# MCUv1_2.net
KiCad netlist of a schematic drawn in Altium Designer
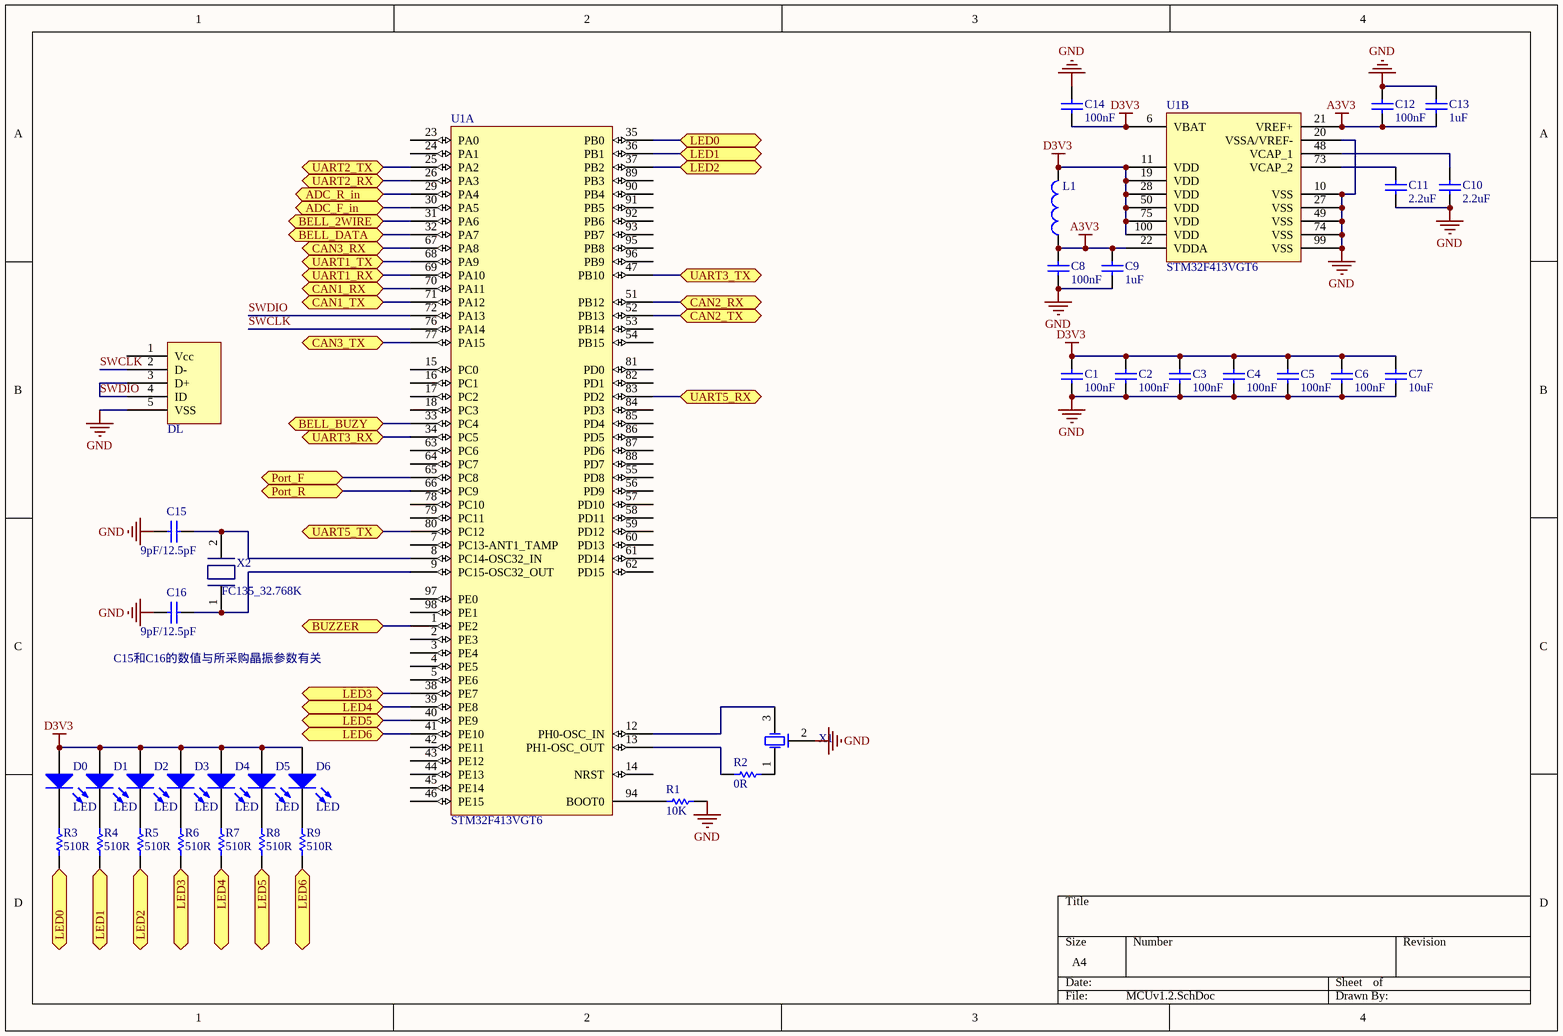
[diagram p0: MCUv1.2.SchDoc]

(export (version "E")
  (design (tool "Eeschema 10.0.6"))
  (components
    (comp (ref "C1")
      (value "100nF")
      (footprint "BinFeng:0402")
      (description "Capacitor")
      (fields (field (name "PUBLISHER") "Altium Limited"))
      (libsource (lib "Miscellaneous Devices") (part "Cap"))
    )
    (comp (ref "C2")
      (value "100nF")
      (footprint "BinFeng:0402")
      (description "Capacitor")
      (fields (field (name "PUBLISHER") "Altium Limited"))
      (libsource (lib "Miscellaneous Devices") (part "Cap"))
    )
    (comp (ref "C3")
      (value "100nF")
      (footprint "BinFeng:0402")
      (description "Capacitor")
      (fields (field (name "PUBLISHER") "Altium Limited"))
      (libsource (lib "Miscellaneous Devices") (part "Cap"))
    )
    (comp (ref "C4")
      (value "100nF")
      (footprint "BinFeng:0402")
      (description "Capacitor")
      (fields (field (name "PUBLISHER") "Altium Limited"))
      (libsource (lib "Miscellaneous Devices") (part "Cap"))
    )
    (comp (ref "C5")
      (value "100nF")
      (footprint "BinFeng:0402")
      (description "Capacitor")
      (fields (field (name "PUBLISHER") "Altium Limited"))
      (libsource (lib "Miscellaneous Devices") (part "Cap"))
    )
    (comp (ref "C6")
      (value "100nF")
      (footprint "BinFeng:0402")
      (description "Capacitor")
      (fields (field (name "PUBLISHER") "Altium Limited"))
      (libsource (lib "Miscellaneous Devices") (part "Cap"))
    )
    (comp (ref "C7")
      (value "10uF")
      (footprint "0805")
      (description "Capacitor")
      (fields (field (name "PUBLISHER") "Altium Limited"))
      (libsource (lib "Miscellaneous Devices") (part "Cap"))
    )
    (comp (ref "C8")
      (value "100nF")
      (footprint "BinFeng:0402")
      (description "Capacitor")
      (fields (field (name "PUBLISHER") "Altium Limited"))
      (libsource (lib "Miscellaneous Devices") (part "Cap"))
    )
    (comp (ref "C9")
      (value "1uF")
      (footprint "BinFeng:0402")
      (description "Capacitor")
      (fields (field (name "PUBLISHER") "Altium Limited"))
      (libsource (lib "Miscellaneous Devices") (part "Cap"))
    )
    (comp (ref "C10")
      (value "2.2uF")
      (footprint "BinFeng:0603")
      (description "Capacitor")
      (fields (field (name "PUBLISHER") "Altium Limited"))
      (libsource (lib "Miscellaneous Devices") (part "Cap"))
    )
    (comp (ref "C11")
      (value "2.2uF")
      (footprint "BinFeng:0603")
      (description "Capacitor")
      (fields (field (name "PUBLISHER") "Altium Limited"))
      (libsource (lib "Miscellaneous Devices") (part "Cap"))
    )
    (comp (ref "C12")
      (value "100nF")
      (footprint "BinFeng:0402")
      (description "Capacitor")
      (fields (field (name "PUBLISHER") "Altium Limited"))
      (libsource (lib "Miscellaneous Devices") (part "Cap"))
    )
    (comp (ref "C13")
      (value "1uF")
      (footprint "BinFeng:0402")
      (description "Capacitor")
      (fields (field (name "PUBLISHER") "Altium Limited"))
      (libsource (lib "Miscellaneous Devices") (part "Cap"))
    )
    (comp (ref "C14")
      (value "100nF")
      (footprint "BinFeng:0402")
      (description "Capacitor")
      (fields (field (name "PUBLISHER") "Altium Limited"))
      (libsource (lib "Miscellaneous Devices") (part "Cap"))
    )
    (comp (ref "C15")
      (value "9pF/12.5pF")
      (footprint "BinFeng:0402")
      (description "Capacitor")
      (fields (field (name "PUBLISHER") "Altium Limited"))
      (libsource (lib "Miscellaneous Devices") (part "Cap"))
    )
    (comp (ref "C16")
      (value "9pF/12.5pF")
      (footprint "BinFeng:0402")
      (description "Capacitor")
      (fields (field (name "PUBLISHER") "Altium Limited"))
      (libsource (lib "Miscellaneous Devices") (part "Cap"))
    )
    (comp (ref "D0")
      (value "LED")
      (footprint "1206")
      (description "green LED")
      (fields (field (name "PUBLISHER") "Altium Limited"))
      (libsource (lib "Miscellaneous Devices") (part "LED0"))
    )
    (comp (ref "D1")
      (value "LED")
      (footprint "1206")
      (description "green LED")
      (fields (field (name "PUBLISHER") "Altium Limited"))
      (libsource (lib "Miscellaneous Devices") (part "LED0"))
    )
    (comp (ref "D2")
      (value "LED")
      (footprint "1206")
      (description "green LED")
      (fields (field (name "PUBLISHER") "Altium Limited"))
      (libsource (lib "Miscellaneous Devices") (part "LED0"))
    )
    (comp (ref "D3")
      (value "LED")
      (footprint "1206")
      (description "green LED")
      (fields (field (name "PUBLISHER") "Altium Limited"))
      (libsource (lib "Miscellaneous Devices") (part "LED0"))
    )
    (comp (ref "D4")
      (value "LED")
      (footprint "1206")
      (description "green LED")
      (fields (field (name "PUBLISHER") "Altium Limited"))
      (libsource (lib "Miscellaneous Devices") (part "LED0"))
    )
    (comp (ref "D5")
      (value "LED")
      (footprint "1206")
      (description "green LED")
      (fields (field (name "PUBLISHER") "Altium Limited"))
      (libsource (lib "Miscellaneous Devices") (part "LED0"))
    )
    (comp (ref "D6")
      (value "LED")
      (footprint "1206")
      (description "green LED")
      (fields (field (name "PUBLISHER") "Altium Limited"))
      (libsource (lib "Miscellaneous Devices") (part "LED0"))
    )
    (comp (ref "DL")
      (value "USB_5pin")
      (footprint "USBmicro_B")
      (libsource (lib "BinFeng_Connectors") (part "USB_5pin"))
    )
    (comp (ref "L1")
      (value "BLM15BD221SN1D")
      (footprint "BinFeng:0402")
      (description "muRata ferrite bead")
      (fields (field (name "PUBLISHER") "Altium Limited"))
      (libsource (lib "Miscellaneous Devices") (part "Inductor"))
    )
    (comp (ref "R1")
      (value "10K")
      (footprint "BinFeng:0402")
      (description "Resistor")
      (fields (field (name "PUBLISHER") "Altium Limited"))
      (libsource (lib "Miscellaneous Devices") (part "Res1"))
    )
    (comp (ref "R2")
      (value "0R")
      (footprint "BinFeng:0402")
      (description "Resistor")
      (fields (field (name "PUBLISHER") "Altium Limited"))
      (libsource (lib "Miscellaneous Devices") (part "Res1"))
    )
    (comp (ref "R3")
      (value "510R")
      (footprint "BinFeng:0402")
      (description "Resistor")
      (fields (field (name "PUBLISHER") "Altium Limited"))
      (libsource (lib "Miscellaneous Devices") (part "Res1"))
    )
    (comp (ref "R4")
      (value "510R")
      (footprint "BinFeng:0402")
      (description "Resistor")
      (fields (field (name "PUBLISHER") "Altium Limited"))
      (libsource (lib "Miscellaneous Devices") (part "Res1"))
    )
    (comp (ref "R5")
      (value "510R")
      (footprint "BinFeng:0402")
      (description "Resistor")
      (fields (field (name "PUBLISHER") "Altium Limited"))
      (libsource (lib "Miscellaneous Devices") (part "Res1"))
    )
    (comp (ref "R6")
      (value "510R")
      (footprint "BinFeng:0402")
      (description "Resistor")
      (fields (field (name "PUBLISHER") "Altium Limited"))
      (libsource (lib "Miscellaneous Devices") (part "Res1"))
    )
    (comp (ref "R7")
      (value "510R")
      (footprint "BinFeng:0402")
      (description "Resistor")
      (fields (field (name "PUBLISHER") "Altium Limited"))
      (libsource (lib "Miscellaneous Devices") (part "Res1"))
    )
    (comp (ref "R8")
      (value "510R")
      (footprint "BinFeng:0402")
      (description "Resistor")
      (fields (field (name "PUBLISHER") "Altium Limited"))
      (libsource (lib "Miscellaneous Devices") (part "Res1"))
    )
    (comp (ref "R9")
      (value "510R")
      (footprint "BinFeng:0402")
      (description "Resistor")
      (fields (field (name "PUBLISHER") "Altium Limited"))
      (libsource (lib "Miscellaneous Devices") (part "Res1"))
    )
    (comp (ref "U1")
      (value "STM32F413VGT6")
      (footprint "STM-LQFP100_V")
      (description "ARM Cortex-M4 32-Bit DSP+FPU, 1024 KB Flash, 82 I/Os, 100-Pin LQFP, -40 to 85 degC, Tray")
      (libsource (lib "Altium Content Vault") (part "STM-STM32F413-LQFP-100"))
    )
    (comp (ref "X1")
      (value "8M smd")
      (footprint "8Mhz_XTAL")
      (description "muRata")
      (libsource (lib "Schlib1") (part "8M smd"))
    )
    (comp (ref "X2")
      (value "FC135_32.768K")
      (footprint "FC135")
      (libsource (lib "BinFeng_IC") (part "XTAL_32.768k"))
    )
  )
  (nets
    (net (code "1") (name "/ADC_F_in") (class "Default")
      (node (ref "U1") (pin "30") (pinfunction "PA5_30") (pintype "bidirectional"))
    )
    (net (code "2") (name "/ADC_R_in") (class "Default")
      (node (ref "U1") (pin "29") (pinfunction "PA4_29") (pintype "bidirectional"))
    )
    (net (code "3") (name "/BELL_2WIRE") (class "Default")
      (node (ref "U1") (pin "31") (pinfunction "PA6_31") (pintype "bidirectional"))
    )
    (net (code "4") (name "/BELL_BUZY") (class "Default")
      (node (ref "U1") (pin "33") (pinfunction "PC4_33") (pintype "bidirectional"))
    )
    (net (code "5") (name "/BELL_DATA") (class "Default")
      (node (ref "U1") (pin "32") (pinfunction "PA7_32") (pintype "bidirectional"))
    )
    (net (code "6") (name "/BUZZER") (class "Default")
      (node (ref "U1") (pin "1") (pinfunction "PE2_1") (pintype "bidirectional"))
    )
    (net (code "7") (name "/CAN1_RX") (class "Default")
      (node (ref "U1") (pin "70") (pinfunction "PA11_70") (pintype "bidirectional"))
    )
    (net (code "8") (name "/CAN1_TX") (class "Default")
      (node (ref "U1") (pin "71") (pinfunction "PA12_71") (pintype "bidirectional"))
    )
    (net (code "9") (name "/CAN2_RX") (class "Default")
      (node (ref "U1") (pin "51") (pinfunction "PB12_51") (pintype "bidirectional"))
    )
    (net (code "10") (name "/CAN2_TX") (class "Default")
      (node (ref "U1") (pin "52") (pinfunction "PB13_52") (pintype "bidirectional"))
    )
    (net (code "11") (name "/CAN3_RX") (class "Default")
      (node (ref "U1") (pin "67") (pinfunction "PA8_67") (pintype "bidirectional"))
    )
    (net (code "12") (name "/CAN3_TX") (class "Default")
      (node (ref "U1") (pin "77") (pinfunction "PA15_77") (pintype "bidirectional"))
    )
    (net (code "13") (name "/LED0") (class "Default")
      (node (ref "R3") (pin "1") (pinfunction "1_1") (pintype "passive"))
      (node (ref "U1") (pin "35") (pinfunction "PB0_35") (pintype "bidirectional"))
    )
    (net (code "14") (name "/LED1") (class "Default")
      (node (ref "R4") (pin "1") (pinfunction "1_1") (pintype "passive"))
      (node (ref "U1") (pin "36") (pinfunction "PB1_36") (pintype "bidirectional"))
    )
    (net (code "15") (name "/LED2") (class "Default")
      (node (ref "R5") (pin "1") (pinfunction "1_1") (pintype "passive"))
      (node (ref "U1") (pin "37") (pinfunction "PB2_37") (pintype "bidirectional"))
    )
    (net (code "16") (name "/LED3") (class "Default")
      (node (ref "R6") (pin "1") (pinfunction "1_1") (pintype "passive"))
      (node (ref "U1") (pin "38") (pinfunction "PE7_38") (pintype "bidirectional"))
    )
    (net (code "17") (name "/LED4") (class "Default")
      (node (ref "R7") (pin "1") (pinfunction "1_1") (pintype "passive"))
      (node (ref "U1") (pin "39") (pinfunction "PE8_39") (pintype "bidirectional"))
    )
    (net (code "18") (name "/LED5") (class "Default")
      (node (ref "R8") (pin "1") (pinfunction "1_1") (pintype "passive"))
      (node (ref "U1") (pin "40") (pinfunction "PE9_40") (pintype "bidirectional"))
    )
    (net (code "19") (name "/LED6") (class "Default")
      (node (ref "R9") (pin "1") (pinfunction "1_1") (pintype "passive"))
      (node (ref "U1") (pin "41") (pinfunction "PE10_41") (pintype "bidirectional"))
    )
    (net (code "20") (name "/Port_F") (class "Default")
      (node (ref "U1") (pin "65") (pinfunction "PC8_65") (pintype "bidirectional"))
    )
    (net (code "21") (name "/Port_R") (class "Default")
      (node (ref "U1") (pin "66") (pinfunction "PC9_66") (pintype "bidirectional"))
    )
    (net (code "22") (name "/SWCLK") (class "Default")
      (node (ref "DL") (pin "2") (pinfunction "D-_2") (pintype "passive"))
      (node (ref "U1") (pin "76") (pinfunction "PA14_76") (pintype "bidirectional"))
    )
    (net (code "23") (name "/SWDIO") (class "Default")
      (node (ref "DL") (pin "3") (pinfunction "D+_3") (pintype "passive"))
      (node (ref "DL") (pin "4") (pinfunction "ID_4") (pintype "passive"))
      (node (ref "U1") (pin "72") (pinfunction "PA13_72") (pintype "bidirectional"))
    )
    (net (code "24") (name "/UART1_RX") (class "Default")
      (node (ref "U1") (pin "69") (pinfunction "PA10_69") (pintype "bidirectional"))
    )
    (net (code "25") (name "/UART1_TX") (class "Default")
      (node (ref "U1") (pin "68") (pinfunction "PA9_68") (pintype "bidirectional"))
    )
    (net (code "26") (name "/UART2_RX") (class "Default")
      (node (ref "U1") (pin "26") (pinfunction "PA3_26") (pintype "bidirectional"))
    )
    (net (code "27") (name "/UART2_TX") (class "Default")
      (node (ref "U1") (pin "25") (pinfunction "PA2_25") (pintype "bidirectional"))
    )
    (net (code "28") (name "/UART3_RX") (class "Default")
      (node (ref "U1") (pin "34") (pinfunction "PC5_34") (pintype "bidirectional"))
    )
    (net (code "29") (name "/UART3_TX") (class "Default")
      (node (ref "U1") (pin "47") (pinfunction "PB10_47") (pintype "bidirectional"))
    )
    (net (code "30") (name "/UART5_RX") (class "Default")
      (node (ref "U1") (pin "83") (pinfunction "PD2_83") (pintype "bidirectional"))
    )
    (net (code "31") (name "/UART5_TX") (class "Default")
      (node (ref "U1") (pin "80") (pinfunction "PC12_80") (pintype "bidirectional"))
    )
    (net (code "32") (name "A3V3") (class "Default")
      (node (ref "C12") (pin "1") (pinfunction "1_1") (pintype "passive"))
      (node (ref "C13") (pin "1") (pinfunction "1_1") (pintype "passive"))
      (node (ref "C8") (pin "2") (pinfunction "2_2") (pintype "passive"))
      (node (ref "C9") (pin "2") (pinfunction "2_2") (pintype "passive"))
      (node (ref "L1") (pin "1") (pinfunction "1_1") (pintype "passive"))
      (node (ref "U1") (pin "21") (pinfunction "VREF+_21") (pintype "power_in"))
      (node (ref "U1") (pin "22") (pinfunction "VDDA_22") (pintype "power_in"))
    )
    (net (code "33") (name "D3V3") (class "Default")
      (node (ref "C1") (pin "2") (pinfunction "2_2") (pintype "passive"))
      (node (ref "C14") (pin "1") (pinfunction "1_1") (pintype "passive"))
      (node (ref "C2") (pin "2") (pinfunction "2_2") (pintype "passive"))
      (node (ref "C3") (pin "2") (pinfunction "2_2") (pintype "passive"))
      (node (ref "C4") (pin "2") (pinfunction "2_2") (pintype "passive"))
      (node (ref "C5") (pin "2") (pinfunction "2_2") (pintype "passive"))
      (node (ref "C6") (pin "2") (pinfunction "2_2") (pintype "passive"))
      (node (ref "C7") (pin "2") (pinfunction "2_2") (pintype "passive"))
      (node (ref "D0") (pin "1") (pinfunction "A_1") (pintype "passive"))
      (node (ref "D1") (pin "1") (pinfunction "A_1") (pintype "passive"))
      (node (ref "D2") (pin "1") (pinfunction "A_1") (pintype "passive"))
      (node (ref "D3") (pin "1") (pinfunction "A_1") (pintype "passive"))
      (node (ref "D4") (pin "1") (pinfunction "A_1") (pintype "passive"))
      (node (ref "D5") (pin "1") (pinfunction "A_1") (pintype "passive"))
      (node (ref "D6") (pin "1") (pinfunction "A_1") (pintype "passive"))
      (node (ref "L1") (pin "2") (pinfunction "2_2") (pintype "passive"))
      (node (ref "U1") (pin "100") (pinfunction "VDD_100") (pintype "power_in"))
      (node (ref "U1") (pin "11") (pinfunction "VDD_11") (pintype "power_in"))
      (node (ref "U1") (pin "19") (pinfunction "VDD_19") (pintype "power_in"))
      (node (ref "U1") (pin "28") (pinfunction "VDD_28") (pintype "power_in"))
      (node (ref "U1") (pin "50") (pinfunction "VDD_50") (pintype "power_in"))
      (node (ref "U1") (pin "6") (pinfunction "VBAT_6") (pintype "power_in"))
      (node (ref "U1") (pin "75") (pinfunction "VDD_75") (pintype "power_in"))
    )
    (net (code "34") (name "GND") (class "Default")
      (node (ref "C1") (pin "1") (pinfunction "1_1") (pintype "passive"))
      (node (ref "C10") (pin "1") (pinfunction "1_1") (pintype "passive"))
      (node (ref "C11") (pin "1") (pinfunction "1_1") (pintype "passive"))
      (node (ref "C12") (pin "2") (pinfunction "2_2") (pintype "passive"))
      (node (ref "C13") (pin "2") (pinfunction "2_2") (pintype "passive"))
      (node (ref "C14") (pin "2") (pinfunction "2_2") (pintype "passive"))
      (node (ref "C15") (pin "2") (pinfunction "2_2") (pintype "passive"))
      (node (ref "C16") (pin "2") (pinfunction "2_2") (pintype "passive"))
      (node (ref "C2") (pin "1") (pinfunction "1_1") (pintype "passive"))
      (node (ref "C3") (pin "1") (pinfunction "1_1") (pintype "passive"))
      (node (ref "C4") (pin "1") (pinfunction "1_1") (pintype "passive"))
      (node (ref "C5") (pin "1") (pinfunction "1_1") (pintype "passive"))
      (node (ref "C6") (pin "1") (pinfunction "1_1") (pintype "passive"))
      (node (ref "C7") (pin "1") (pinfunction "1_1") (pintype "passive"))
      (node (ref "C8") (pin "1") (pinfunction "1_1") (pintype "passive"))
      (node (ref "C9") (pin "1") (pinfunction "1_1") (pintype "passive"))
      (node (ref "DL") (pin "5") (pinfunction "VSS_5") (pintype "passive"))
      (node (ref "R1") (pin "2") (pinfunction "2_2") (pintype "passive"))
      (node (ref "U1") (pin "10") (pinfunction "VSS_10") (pintype "power_in"))
      (node (ref "U1") (pin "20") (pinfunction "VSSA/VREF-_20") (pintype "power_in"))
      (node (ref "U1") (pin "27") (pinfunction "VSS_27") (pintype "power_in"))
      (node (ref "U1") (pin "49") (pinfunction "VSS_49") (pintype "power_in"))
      (node (ref "U1") (pin "74") (pinfunction "VSS_74") (pintype "power_in"))
      (node (ref "U1") (pin "99") (pinfunction "VSS_99") (pintype "power_in"))
      (node (ref "X1") (pin "2") (pinfunction "GND_2") (pintype "passive"))
    )
    (net (code "35") (name "Net-(D0-K)") (class "Default")
      (node (ref "D0") (pin "2") (pinfunction "K_2") (pintype "passive"))
      (node (ref "R3") (pin "2") (pinfunction "2_2") (pintype "passive"))
    )
    (net (code "36") (name "Net-(D1-K)") (class "Default")
      (node (ref "D1") (pin "2") (pinfunction "K_2") (pintype "passive"))
      (node (ref "R4") (pin "2") (pinfunction "2_2") (pintype "passive"))
    )
    (net (code "37") (name "Net-(D2-K)") (class "Default")
      (node (ref "D2") (pin "2") (pinfunction "K_2") (pintype "passive"))
      (node (ref "R5") (pin "2") (pinfunction "2_2") (pintype "passive"))
    )
    (net (code "38") (name "Net-(D3-K)") (class "Default")
      (node (ref "D3") (pin "2") (pinfunction "K_2") (pintype "passive"))
      (node (ref "R6") (pin "2") (pinfunction "2_2") (pintype "passive"))
    )
    (net (code "39") (name "Net-(D4-K)") (class "Default")
      (node (ref "D4") (pin "2") (pinfunction "K_2") (pintype "passive"))
      (node (ref "R7") (pin "2") (pinfunction "2_2") (pintype "passive"))
    )
    (net (code "40") (name "Net-(D5-K)") (class "Default")
      (node (ref "D5") (pin "2") (pinfunction "K_2") (pintype "passive"))
      (node (ref "R8") (pin "2") (pinfunction "2_2") (pintype "passive"))
    )
    (net (code "41") (name "Net-(D6-K)") (class "Default")
      (node (ref "D6") (pin "2") (pinfunction "K_2") (pintype "passive"))
      (node (ref "R9") (pin "2") (pinfunction "2_2") (pintype "passive"))
    )
    (net (code "42") (name "Net-(U1A-BOOT0)") (class "Default")
      (node (ref "R1") (pin "1") (pinfunction "1_1") (pintype "passive"))
      (node (ref "U1") (pin "94") (pinfunction "BOOT0_94") (pintype "passive"))
    )
    (net (code "43") (name "Net-(U1A-PC14-OSC32_IN)") (class "Default")
      (node (ref "C15") (pin "1") (pinfunction "1_1") (pintype "passive"))
      (node (ref "U1") (pin "8") (pinfunction "PC14-OSC32_IN_8") (pintype "bidirectional"))
      (node (ref "X2") (pin "2") (pinfunction "2_2") (pintype "passive"))
    )
    (net (code "44") (name "Net-(U1A-PC15-OSC32_OUT)") (class "Default")
      (node (ref "C16") (pin "1") (pinfunction "1_1") (pintype "passive"))
      (node (ref "U1") (pin "9") (pinfunction "PC15-OSC32_OUT_9") (pintype "bidirectional"))
      (node (ref "X2") (pin "1") (pinfunction "1_1") (pintype "passive"))
    )
    (net (code "45") (name "Net-(U1A-PH0-OSC_IN)") (class "Default")
      (node (ref "U1") (pin "12") (pinfunction "PH0-OSC_IN_12") (pintype "bidirectional"))
      (node (ref "X1") (pin "3") (pinfunction "OSC2_3") (pintype "passive"))
    )
    (net (code "46") (name "Net-(U1A-PH1-OSC_OUT)") (class "Default")
      (node (ref "R2") (pin "2") (pinfunction "2_2") (pintype "passive"))
      (node (ref "U1") (pin "13") (pinfunction "PH1-OSC_OUT_13") (pintype "bidirectional"))
    )
    (net (code "47") (name "Net-(U1B-VCAP_1)") (class "Default")
      (node (ref "C10") (pin "2") (pinfunction "2_2") (pintype "passive"))
      (node (ref "U1") (pin "48") (pinfunction "VCAP_1_48") (pintype "passive"))
    )
    (net (code "48") (name "Net-(U1B-VCAP_2)") (class "Default")
      (node (ref "C11") (pin "2") (pinfunction "2_2") (pintype "passive"))
      (node (ref "U1") (pin "73") (pinfunction "VCAP_2_73") (pintype "passive"))
    )
    (net (code "49") (name "Net-(X1-OSC1)") (class "Default")
      (node (ref "R2") (pin "1") (pinfunction "1_1") (pintype "passive"))
      (node (ref "X1") (pin "1") (pinfunction "OSC1_1") (pintype "passive"))
    )
    (net (code "50") (name "unconnected-(DL-Vcc-Pad1)") (class "Default")
      (node (ref "DL") (pin "1") (pinfunction "Vcc_1") (pintype "passive"))
    )
    (net (code "51") (name "unconnected-(U1A-NRST-Pad14)") (class "Default")
      (node (ref "U1") (pin "14") (pinfunction "NRST_14") (pintype "bidirectional"))
    )
    (net (code "52") (name "unconnected-(U1A-PA0-Pad23)") (class "Default")
      (node (ref "U1") (pin "23") (pinfunction "PA0_23") (pintype "bidirectional"))
    )
    (net (code "53") (name "unconnected-(U1A-PA1-Pad24)") (class "Default")
      (node (ref "U1") (pin "24") (pinfunction "PA1_24") (pintype "bidirectional"))
    )
    (net (code "54") (name "unconnected-(U1A-PB3-Pad89)") (class "Default")
      (node (ref "U1") (pin "89") (pinfunction "PB3_89") (pintype "bidirectional"))
    )
    (net (code "55") (name "unconnected-(U1A-PB4-Pad90)") (class "Default")
      (node (ref "U1") (pin "90") (pinfunction "PB4_90") (pintype "bidirectional"))
    )
    (net (code "56") (name "unconnected-(U1A-PB5-Pad91)") (class "Default")
      (node (ref "U1") (pin "91") (pinfunction "PB5_91") (pintype "bidirectional"))
    )
    (net (code "57") (name "unconnected-(U1A-PB6-Pad92)") (class "Default")
      (node (ref "U1") (pin "92") (pinfunction "PB6_92") (pintype "bidirectional"))
    )
    (net (code "58") (name "unconnected-(U1A-PB7-Pad93)") (class "Default")
      (node (ref "U1") (pin "93") (pinfunction "PB7_93") (pintype "bidirectional"))
    )
    (net (code "59") (name "unconnected-(U1A-PB8-Pad95)") (class "Default")
      (node (ref "U1") (pin "95") (pinfunction "PB8_95") (pintype "bidirectional"))
    )
    (net (code "60") (name "unconnected-(U1A-PB9-Pad96)") (class "Default")
      (node (ref "U1") (pin "96") (pinfunction "PB9_96") (pintype "bidirectional"))
    )
    (net (code "61") (name "unconnected-(U1A-PB14-Pad53)") (class "Default")
      (node (ref "U1") (pin "53") (pinfunction "PB14_53") (pintype "bidirectional"))
    )
    (net (code "62") (name "unconnected-(U1A-PB15-Pad54)") (class "Default")
      (node (ref "U1") (pin "54") (pinfunction "PB15_54") (pintype "bidirectional"))
    )
    (net (code "63") (name "unconnected-(U1A-PC0-Pad15)") (class "Default")
      (node (ref "U1") (pin "15") (pinfunction "PC0_15") (pintype "bidirectional"))
    )
    (net (code "64") (name "unconnected-(U1A-PC1-Pad16)") (class "Default")
      (node (ref "U1") (pin "16") (pinfunction "PC1_16") (pintype "bidirectional"))
    )
    (net (code "65") (name "unconnected-(U1A-PC2-Pad17)") (class "Default")
      (node (ref "U1") (pin "17") (pinfunction "PC2_17") (pintype "bidirectional"))
    )
    (net (code "66") (name "unconnected-(U1A-PC3-Pad18)") (class "Default")
      (node (ref "U1") (pin "18") (pinfunction "PC3_18") (pintype "bidirectional"))
    )
    (net (code "67") (name "unconnected-(U1A-PC6-Pad63)") (class "Default")
      (node (ref "U1") (pin "63") (pinfunction "PC6_63") (pintype "bidirectional"))
    )
    (net (code "68") (name "unconnected-(U1A-PC7-Pad64)") (class "Default")
      (node (ref "U1") (pin "64") (pinfunction "PC7_64") (pintype "bidirectional"))
    )
    (net (code "69") (name "unconnected-(U1A-PC10-Pad78)") (class "Default")
      (node (ref "U1") (pin "78") (pinfunction "PC10_78") (pintype "bidirectional"))
    )
    (net (code "70") (name "unconnected-(U1A-PC11-Pad79)") (class "Default")
      (node (ref "U1") (pin "79") (pinfunction "PC11_79") (pintype "bidirectional"))
    )
    (net (code "71") (name "unconnected-(U1A-PC13-ANT1_TAMP-Pad7)") (class "Default")
      (node (ref "U1") (pin "7") (pinfunction "PC13-ANT1_TAMP_7") (pintype "bidirectional"))
    )
    (net (code "72") (name "unconnected-(U1A-PD0-Pad81)") (class "Default")
      (node (ref "U1") (pin "81") (pinfunction "PD0_81") (pintype "bidirectional"))
    )
    (net (code "73") (name "unconnected-(U1A-PD1-Pad82)") (class "Default")
      (node (ref "U1") (pin "82") (pinfunction "PD1_82") (pintype "bidirectional"))
    )
    (net (code "74") (name "unconnected-(U1A-PD3-Pad84)") (class "Default")
      (node (ref "U1") (pin "84") (pinfunction "PD3_84") (pintype "bidirectional"))
    )
    (net (code "75") (name "unconnected-(U1A-PD4-Pad85)") (class "Default")
      (node (ref "U1") (pin "85") (pinfunction "PD4_85") (pintype "bidirectional"))
    )
    (net (code "76") (name "unconnected-(U1A-PD5-Pad86)") (class "Default")
      (node (ref "U1") (pin "86") (pinfunction "PD5_86") (pintype "bidirectional"))
    )
    (net (code "77") (name "unconnected-(U1A-PD6-Pad87)") (class "Default")
      (node (ref "U1") (pin "87") (pinfunction "PD6_87") (pintype "bidirectional"))
    )
    (net (code "78") (name "unconnected-(U1A-PD7-Pad88)") (class "Default")
      (node (ref "U1") (pin "88") (pinfunction "PD7_88") (pintype "bidirectional"))
    )
    (net (code "79") (name "unconnected-(U1A-PD8-Pad55)") (class "Default")
      (node (ref "U1") (pin "55") (pinfunction "PD8_55") (pintype "bidirectional"))
    )
    (net (code "80") (name "unconnected-(U1A-PD9-Pad56)") (class "Default")
      (node (ref "U1") (pin "56") (pinfunction "PD9_56") (pintype "bidirectional"))
    )
    (net (code "81") (name "unconnected-(U1A-PD10-Pad57)") (class "Default")
      (node (ref "U1") (pin "57") (pinfunction "PD10_57") (pintype "bidirectional"))
    )
    (net (code "82") (name "unconnected-(U1A-PD11-Pad58)") (class "Default")
      (node (ref "U1") (pin "58") (pinfunction "PD11_58") (pintype "bidirectional"))
    )
    (net (code "83") (name "unconnected-(U1A-PD12-Pad59)") (class "Default")
      (node (ref "U1") (pin "59") (pinfunction "PD12_59") (pintype "bidirectional"))
    )
    (net (code "84") (name "unconnected-(U1A-PD13-Pad60)") (class "Default")
      (node (ref "U1") (pin "60") (pinfunction "PD13_60") (pintype "bidirectional"))
    )
    (net (code "85") (name "unconnected-(U1A-PD14-Pad61)") (class "Default")
      (node (ref "U1") (pin "61") (pinfunction "PD14_61") (pintype "bidirectional"))
    )
    (net (code "86") (name "unconnected-(U1A-PD15-Pad62)") (class "Default")
      (node (ref "U1") (pin "62") (pinfunction "PD15_62") (pintype "bidirectional"))
    )
    (net (code "87") (name "unconnected-(U1A-PE0-Pad97)") (class "Default")
      (node (ref "U1") (pin "97") (pinfunction "PE0_97") (pintype "bidirectional"))
    )
    (net (code "88") (name "unconnected-(U1A-PE1-Pad98)") (class "Default")
      (node (ref "U1") (pin "98") (pinfunction "PE1_98") (pintype "bidirectional"))
    )
    (net (code "89") (name "unconnected-(U1A-PE3-Pad2)") (class "Default")
      (node (ref "U1") (pin "2") (pinfunction "PE3_2") (pintype "bidirectional"))
    )
    (net (code "90") (name "unconnected-(U1A-PE4-Pad3)") (class "Default")
      (node (ref "U1") (pin "3") (pinfunction "PE4_3") (pintype "bidirectional"))
    )
    (net (code "91") (name "unconnected-(U1A-PE5-Pad4)") (class "Default")
      (node (ref "U1") (pin "4") (pinfunction "PE5_4") (pintype "bidirectional"))
    )
    (net (code "92") (name "unconnected-(U1A-PE6-Pad5)") (class "Default")
      (node (ref "U1") (pin "5") (pinfunction "PE6_5") (pintype "bidirectional"))
    )
    (net (code "93") (name "unconnected-(U1A-PE11-Pad42)") (class "Default")
      (node (ref "U1") (pin "42") (pinfunction "PE11_42") (pintype "bidirectional"))
    )
    (net (code "94") (name "unconnected-(U1A-PE12-Pad43)") (class "Default")
      (node (ref "U1") (pin "43") (pinfunction "PE12_43") (pintype "bidirectional"))
    )
    (net (code "95") (name "unconnected-(U1A-PE13-Pad44)") (class "Default")
      (node (ref "U1") (pin "44") (pinfunction "PE13_44") (pintype "bidirectional"))
    )
    (net (code "96") (name "unconnected-(U1A-PE14-Pad45)") (class "Default")
      (node (ref "U1") (pin "45") (pinfunction "PE14_45") (pintype "bidirectional"))
    )
    (net (code "97") (name "unconnected-(U1A-PE15-Pad46)") (class "Default")
      (node (ref "U1") (pin "46") (pinfunction "PE15_46") (pintype "bidirectional"))
    )
  )
)
